# motordriver_left_side.net
KiCad netlist of a schematic drawn in Altium Designer
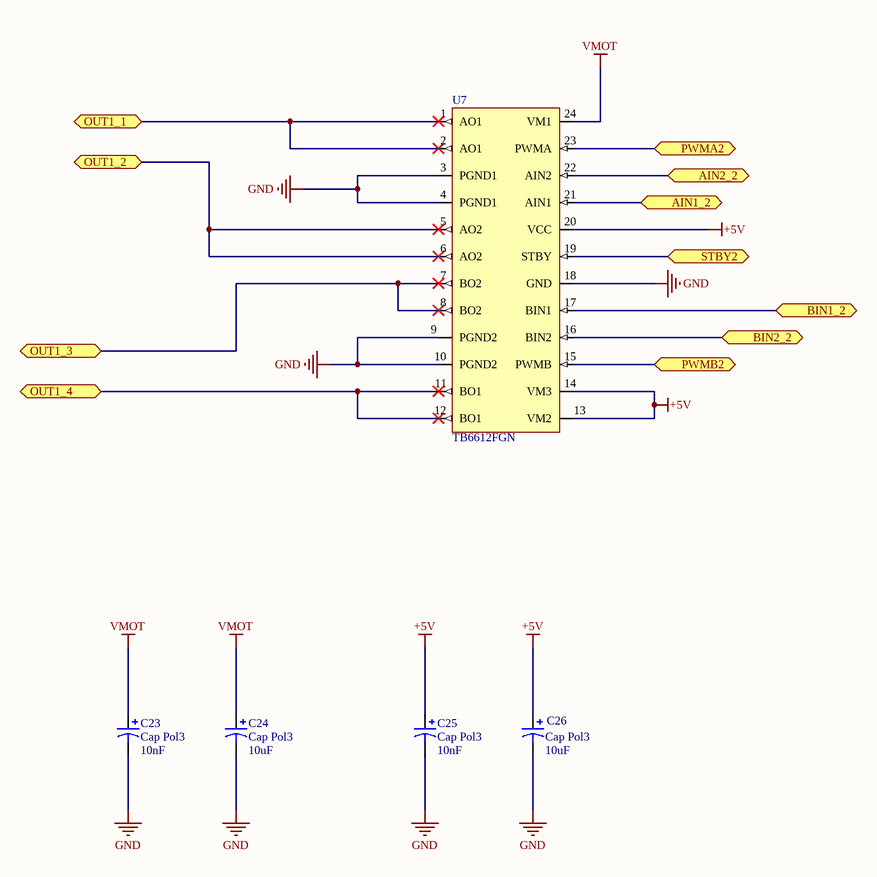
[diagram p0: motordriver left side.SchDoc]

(export (version "E")
  (design (tool "Eeschema 10.0.6"))
  (components
    (comp (ref "C23")
      (value "Cap Pol3")
      (footprint "C0805")
      (description "Polarized Capacitor (Surface Mount)")
      (fields (field (name "ALTIUM_VALUE") "10nF") (field (name "PUBLISHER") "Altium Limited"))
      (libsource (lib "Miscellaneous Devices") (part "Cap Pol3"))
    )
    (comp (ref "C24")
      (value "Cap Pol3")
      (footprint "C0805")
      (description "Polarized Capacitor (Surface Mount)")
      (fields (field (name "ALTIUM_VALUE") "10uF") (field (name "PUBLISHER") "Altium Limited"))
      (libsource (lib "Miscellaneous Devices") (part "Cap Pol3"))
    )
    (comp (ref "C25")
      (value "Cap Pol3")
      (footprint "C0805")
      (description "Polarized Capacitor (Surface Mount)")
      (fields (field (name "ALTIUM_VALUE") "10nF") (field (name "PUBLISHER") "Altium Limited"))
      (libsource (lib "Miscellaneous Devices") (part "Cap Pol3"))
    )
    (comp (ref "C26")
      (value "Cap Pol3")
      (footprint "C0805")
      (description "Polarized Capacitor (Surface Mount)")
      (fields (field (name "ALTIUM_VALUE") "10uF") (field (name "PUBLISHER") "Altium Limited"))
      (libsource (lib "Miscellaneous Devices") (part "Cap Pol3"))
    )
    (comp (ref "U7")
      (value "TB6612FGN")
      (footprint "TBS6612FNG")
      (libsource (lib "TB6612FNGSCHLIB") (part "TB6612FGN"))
    )
  )
  (nets
    (net (code "1") (name "+5V") (class "Default")
      (node (ref "C25") (pin "1") (pinfunction "1_1") (pintype "passive"))
      (node (ref "C26") (pin "1") (pinfunction "1_1") (pintype "passive"))
      (node (ref "U7") (pin "13") (pinfunction "VM2_13") (pintype "passive"))
      (node (ref "U7") (pin "14") (pinfunction "VM3_14") (pintype "passive"))
      (node (ref "U7") (pin "20") (pinfunction "VCC_20") (pintype "passive"))
    )
    (net (code "2") (name "/AIN1_2") (class "Default")
      (node (ref "U7") (pin "21") (pinfunction "AIN1_21") (pintype "input"))
    )
    (net (code "3") (name "/AIN2_2") (class "Default")
      (node (ref "U7") (pin "22") (pinfunction "AIN2_22") (pintype "input"))
    )
    (net (code "4") (name "/BIN1_2") (class "Default")
      (node (ref "U7") (pin "17") (pinfunction "BIN1_17") (pintype "input"))
    )
    (net (code "5") (name "/BIN2_2") (class "Default")
      (node (ref "U7") (pin "16") (pinfunction "BIN2_16") (pintype "input"))
    )
    (net (code "6") (name "/OUT1_1") (class "Default")
      (node (ref "U7") (pin "1") (pinfunction "AO1_1") (pintype "output"))
      (node (ref "U7") (pin "2") (pinfunction "AO1_2") (pintype "output"))
    )
    (net (code "7") (name "/OUT1_2") (class "Default")
      (node (ref "U7") (pin "5") (pinfunction "AO2_5") (pintype "output"))
      (node (ref "U7") (pin "6") (pinfunction "AO2_6") (pintype "output"))
    )
    (net (code "8") (name "/OUT1_3") (class "Default")
      (node (ref "U7") (pin "7") (pinfunction "BO2_7") (pintype "output"))
      (node (ref "U7") (pin "8") (pinfunction "BO2_8") (pintype "output"))
    )
    (net (code "9") (name "/OUT1_4") (class "Default")
      (node (ref "U7") (pin "11") (pinfunction "BO1_11") (pintype "output"))
      (node (ref "U7") (pin "12") (pinfunction "BO1_12") (pintype "output"))
    )
    (net (code "10") (name "/PWMA2") (class "Default")
      (node (ref "U7") (pin "23") (pinfunction "PWMA_23") (pintype "input"))
    )
    (net (code "11") (name "/PWMB2") (class "Default")
      (node (ref "U7") (pin "15") (pinfunction "PWMB_15") (pintype "input"))
    )
    (net (code "12") (name "/STBY2") (class "Default")
      (node (ref "U7") (pin "19") (pinfunction "STBY_19") (pintype "input"))
    )
    (net (code "13") (name "GND") (class "Default")
      (node (ref "C23") (pin "2") (pinfunction "2_2") (pintype "passive"))
      (node (ref "C24") (pin "2") (pinfunction "2_2") (pintype "passive"))
      (node (ref "C25") (pin "2") (pinfunction "2_2") (pintype "passive"))
      (node (ref "C26") (pin "2") (pinfunction "2_2") (pintype "passive"))
      (node (ref "U7") (pin "10") (pinfunction "PGND2_10") (pintype "passive"))
      (node (ref "U7") (pin "18") (pinfunction "GND_18") (pintype "passive"))
      (node (ref "U7") (pin "3") (pinfunction "PGND1_3") (pintype "passive"))
      (node (ref "U7") (pin "4") (pinfunction "PGND1_4") (pintype "passive"))
      (node (ref "U7") (pin "9") (pinfunction "PGND2_9") (pintype "passive"))
    )
    (net (code "14") (name "VMOT") (class "Default")
      (node (ref "C23") (pin "1") (pinfunction "1_1") (pintype "passive"))
      (node (ref "C24") (pin "1") (pinfunction "1_1") (pintype "passive"))
      (node (ref "U7") (pin "24") (pinfunction "VM1_24") (pintype "passive"))
    )
  )
)
